# 01-Insence_Power.net
KiCad netlist of a schematic drawn in Altium Designer
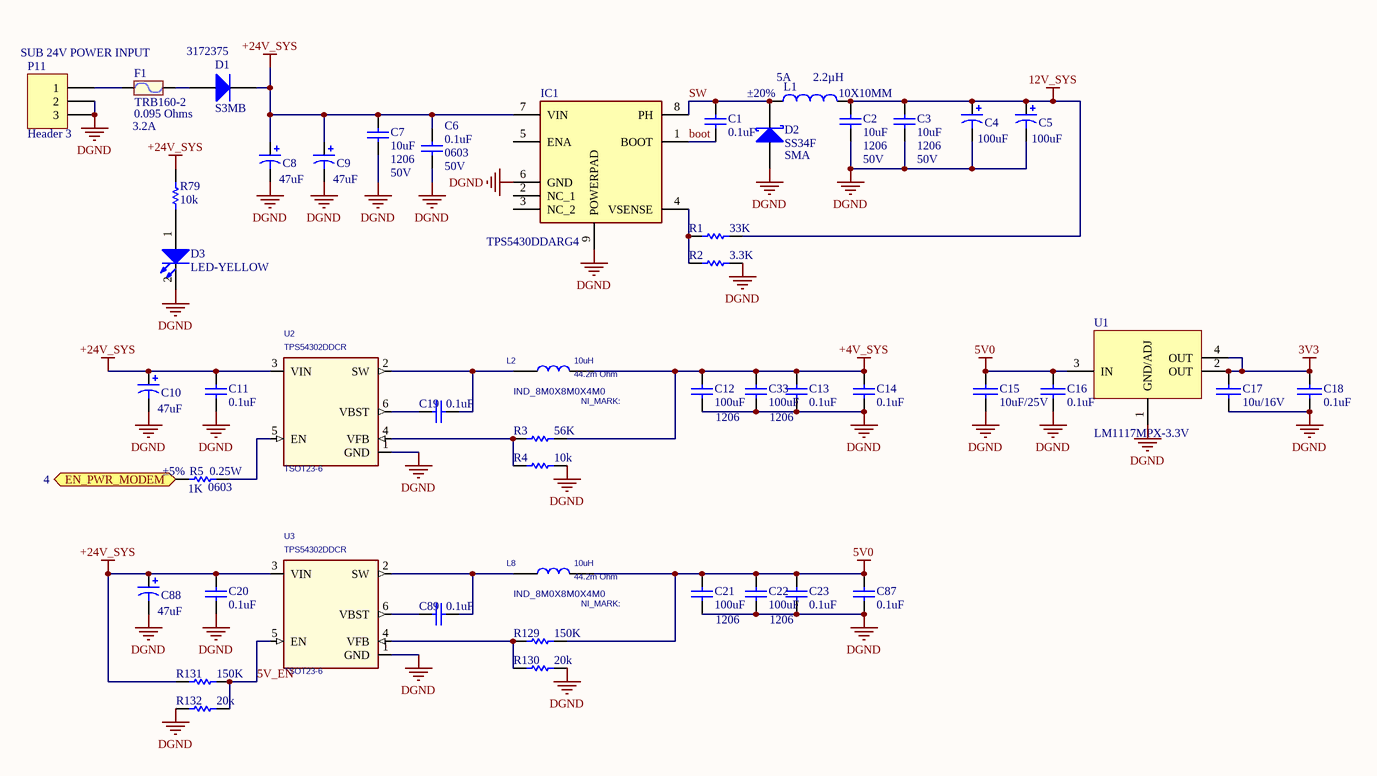
[diagram p0: 01-Insence_Power.SchDoc]

(export (version "E")
  (design (tool "Eeschema 10.0.6"))
  (components
    (comp (ref "C1")
      (value "Cap")
      (footprint "0805")
      (description "CAP CER 0.1UF 50V X7R 0805")
      (fields
        (field (name "=VALUE") "0.1uF")
        (field (name "MANUFACTURER1_PART#") "GMC21X7R104M50NT")
        (field (name "PUBLISHER") "Altium Limited")
      )
      (libsource (lib "Miscellaneous Devices") (part "Cap"))
    )
    (comp (ref "C2")
      (value "10uF")
      (footprint "1206")
      (description "CAP CER 10UF 50V X5R 1206")
      (fields
        (field (name "VOLTAGE") "50V")
        (field (name "TOLERANCE") "±10%")
        (field (name "MANUFACTURER1_PART#") "CL31A106MBHNNNE")
      )
      (libsource (lib "Slider") (part "Cap"))
    )
    (comp (ref "C3")
      (value "10uF")
      (footprint "1206")
      (description "CAP CER 10UF 50V X5R 1206")
      (fields
        (field (name "VOLTAGE") "50V")
        (field (name "TOLERANCE") "±10%")
        (field (name "MANUFACTURER1_PART#") "CL31A106MBHNNNE")
      )
      (libsource (lib "Slider") (part "Cap"))
    )
    (comp (ref "C4")
      (value "100uF")
      (footprint "CAP ALUM SMD-D Package 6.3x5.4mm")
      (description "CAP ALUM 100UF 20% 16V SMD")
      (fields
        (field (name "MANUFACTURER1_PART#") "UWX1C101MCL1GB")
        (field (name "MANUFACTURER2_PART#") "EDK107M016A9GAA")
      )
      (libsource (lib "My Library") (part "Cap TANTAN 100UF35V2917_1"))
    )
    (comp (ref "C5")
      (value "100uF")
      (footprint "CAP ALUM SMD-D Package 6.3x5.4mm")
      (description "CAP ALUM 100UF 20% 16V SMD")
      (fields
        (field (name "MANUFACTURER1_PART#") "UWX1C101MCL1GB")
        (field (name "MANUFACTURER2_PART#") "EDK107M016A9GAA")
      )
      (libsource (lib "My Library") (part "Cap TANTAN 100UF35V2917_1"))
    )
    (comp (ref "C6")
      (value "0.1uF")
      (footprint "0603")
      (description "CAP-CER,SMD;0.1UF,10%,50V,X7R,0603")
      (fields
        (field (name "VOLTAGE") "50V")
        (field (name "TOLERANCE") "±10%")
        (field (name "MANUFACTURER1_PART#") "CL10B104KB8NNNC")
      )
      (libsource (lib "Slider") (part "Cap"))
    )
    (comp (ref "C7")
      (value "10uF")
      (footprint "1206")
      (description "CAP CER 10UF 50V X5R 1206")
      (fields
        (field (name "VOLTAGE") "50V")
        (field (name "TOLERANCE") "±10%")
        (field (name "MANUFACTURER1_PART#") "CL31A106MBHNNNE")
      )
      (libsource (lib "Slider") (part "Cap"))
    )
    (comp (ref "C8")
      (value "47uF")
      (footprint "CAP ALUM SMD-D Package 6.3x5.4mm")
      (description "CAP ALUM 47UF 20% 35V SMD")
      (fields
        (field (name "MANUFACTURER1_PART#") "UUR1V470MCL6GS")
        (field (name "MANUFACTURER2_PART#") "EDK476M035A9GAA")
      )
      (libsource (lib "My Library") (part "Cap TANTAN 47UF35V2917"))
    )
    (comp (ref "C9")
      (value "47uF")
      (footprint "CAP ALUM SMD-D Package 6.3x5.4mm")
      (description "CAP ALUM 47UF 20% 35V SMD")
      (fields
        (field (name "MANUFACTURER1_PART#") "UUR1V470MCL6GS")
        (field (name "MANUFACTURER2_PART#") "EDK476M035A9GAA")
      )
      (libsource (lib "My Library") (part "Cap TANTAN 47UF35V2917"))
    )
    (comp (ref "C10")
      (value "47uF")
      (footprint "CAP ALUM SMD-D Package 6.3x5.4mm")
      (description "CAP ALUM 47UF 20% 35V SMD")
      (fields
        (field (name "MANUFACTURER1_PART#") "UUR1V470MCL6GS")
        (field (name "MANUFACTURER2_PART#") "EDK476M035A9GAA")
      )
      (libsource (lib "My Library") (part "Cap TANTAN 47UF35V2917"))
    )
    (comp (ref "C11")
      (value "Cap")
      (footprint "0805")
      (description "CAP CER 0.1UF 50V X7R 0805")
      (fields
        (field (name "=VALUE") "0.1uF")
        (field (name "MANUFACTURER1_PART#") "GMC21X7R104M50NT")
        (field (name "PUBLISHER") "Altium Limited")
      )
      (libsource (lib "Miscellaneous Devices") (part "Cap"))
    )
    (comp (ref "C12")
      (value "100uF")
      (footprint "CAP 1206")
      (description "CAP CER 100UF 6.3V X5R 1206")
      (fields
        (field (name "VOLTAGE") "6.3V")
        (field (name "PCB FOOTPRINT") "1206")
        (field (name "TOLERANCE") "±10%")
      )
      (libsource (lib "Slider") (part "Cap"))
    )
    (comp (ref "C13")
      (value "Cap")
      (footprint "0805")
      (description "CAP CER 0.1UF 50V X7R 0805")
      (fields
        (field (name "=VALUE") "0.1uF")
        (field (name "MANUFACTURER1_PART#") "GMC21X7R104M50NT")
        (field (name "PUBLISHER") "Altium Limited")
      )
      (libsource (lib "Miscellaneous Devices") (part "Cap"))
    )
    (comp (ref "C14")
      (value "Cap")
      (footprint "0805")
      (description "CAP CER 0.1UF 50V X7R 0805")
      (fields
        (field (name "=VALUE") "0.1uF")
        (field (name "MANUFACTURER1_PART#") "GMC21X7R104M50NT")
        (field (name "PUBLISHER") "Altium Limited")
      )
      (libsource (lib "Miscellaneous Devices") (part "Cap"))
    )
    (comp (ref "C15")
      (value "10uF/25V")
      (footprint "0805")
      (description "CAP CER 10UF 25V X5R 0805")
      (fields (field (name "MANUFACTURER1_PART#") "GMC21X5R106M25NT"))
      (libsource (lib "minhpv_sch") (part "CAP"))
    )
    (comp (ref "C16")
      (value "0.1uF")
      (footprint "0805")
      (description "CAP CER 0.1UF 50V X7R 0805")
      (fields (field (name "MANUFACTURER1_PART#") "GMC21X7R104M50NT"))
      (libsource (lib "minhpv_sch") (part "CAP"))
    )
    (comp (ref "C17")
      (value "10u/16V")
      (footprint "0805")
      (description "CAP CER 10UF 16V X5R 0805")
      (fields (field (name "MANUFACTURER1_PART#") "GMC21X5R106K16NT"))
      (libsource (lib "minhpv_sch") (part "CAP"))
    )
    (comp (ref "C18")
      (value "0.1uF")
      (footprint "0805")
      (description "CAP CER 0.1UF 50V X7R 0805")
      (fields (field (name "MANUFACTURER1_PART#") "GMC21X7R104M50NT"))
      (libsource (lib "minhpv_sch") (part "CAP"))
    )
    (comp (ref "C19")
      (value "Cap")
      (footprint "CAP 0603")
      (description "CAP CER 0.1UF 50V X5R 0603")
      (fields
        (field (name "=VALUE") "0.1uF")
        (field (name "MANUFACTURER1_PART#") "GMC10X5R104M50NT")
        (field (name "PUBLISHER") "Altium Limited")
      )
      (libsource (lib "Miscellaneous Devices") (part "Cap"))
    )
    (comp (ref "C20")
      (value "Cap")
      (footprint "0805")
      (description "CAP CER 0.1UF 50V X7R 0805")
      (fields
        (field (name "=VALUE") "0.1uF")
        (field (name "MANUFACTURER1_PART#") "GMC21X7R104M50NT")
        (field (name "PUBLISHER") "Altium Limited")
      )
      (libsource (lib "Miscellaneous Devices") (part "Cap"))
    )
    (comp (ref "C21")
      (value "100uF")
      (footprint "CAP 1206")
      (description "CAP CER 100UF 6.3V X5R 1206")
      (fields
        (field (name "VOLTAGE") "6.3V")
        (field (name "PCB FOOTPRINT") "1206")
        (field (name "TOLERANCE") "±10%")
      )
      (libsource (lib "Slider") (part "Cap"))
    )
    (comp (ref "C22")
      (value "100uF")
      (footprint "CAP 1206")
      (description "CAP CER 100UF 6.3V X5R 1206")
      (fields
        (field (name "VOLTAGE") "6.3V")
        (field (name "PCB FOOTPRINT") "1206")
        (field (name "TOLERANCE") "±10%")
      )
      (libsource (lib "Slider") (part "Cap"))
    )
    (comp (ref "C23")
      (value "Cap")
      (footprint "0805")
      (description "CAP CER 0.1UF 50V X7R 0805")
      (fields
        (field (name "=VALUE") "0.1uF")
        (field (name "MANUFACTURER1_PART#") "GMC21X7R104M50NT")
        (field (name "PUBLISHER") "Altium Limited")
      )
      (libsource (lib "Miscellaneous Devices") (part "Cap"))
    )
    (comp (ref "C33")
      (value "100uF")
      (footprint "CAP 1206")
      (description "CAP CER 100UF 6.3V X5R 1206")
      (fields
        (field (name "VOLTAGE") "6.3V")
        (field (name "PCB FOOTPRINT") "1206")
        (field (name "TOLERANCE") "±10%")
      )
      (libsource (lib "Slider") (part "Cap"))
    )
    (comp (ref "C87")
      (value "Cap")
      (footprint "0805")
      (description "CAP CER 0.1UF 50V X7R 0805")
      (fields
        (field (name "=VALUE") "0.1uF")
        (field (name "MANUFACTURER1_PART#") "GMC21X7R104M50NT")
        (field (name "PUBLISHER") "Altium Limited")
      )
      (libsource (lib "Miscellaneous Devices") (part "Cap"))
    )
    (comp (ref "C88")
      (value "47uF")
      (footprint "CAP ALUM SMD-D Package 6.3x5.4mm")
      (description "CAP ALUM 47UF 20% 35V SMD")
      (fields
        (field (name "MANUFACTURER1_PART#") "UUR1V470MCL6GS")
        (field (name "MANUFACTURER2_PART#") "EDK476M035A9GAA")
      )
      (libsource (lib "My Library") (part "Cap TANTAN 47UF35V2917"))
    )
    (comp (ref "C89")
      (value "Cap")
      (footprint "CAP 0603")
      (description "CAP CER 0.1UF 50V X5R 0603")
      (fields
        (field (name "=VALUE") "0.1uF")
        (field (name "MANUFACTURER1_PART#") "GMC10X5R104M50NT")
        (field (name "PUBLISHER") "Altium Limited")
      )
      (libsource (lib "Miscellaneous Devices") (part "Cap"))
    )
    (comp (ref "D1")
      (value "S3MB")
      (footprint "DO-214AB")
      (description "Default Diode")
      (fields
        (field (name "MANUFACTURER1_PART#") "S3MB-13-F")
        (field (name "SUPPLIER PART NUMBER 1") "3172375")
        (field (name "PUBLISHER") "Altium Limited")
      )
      (libsource (lib "Miscellaneous Devices") (part "Diode"))
    )
    (comp (ref "D2")
      (value "SS34F")
      (footprint "SMA")
      (description "Diode 40 V 3A Surface Mount SMAF")
      (fields (field (name "PACKAGEREFERENCE") "SMA") (field (name "PUBLISHER") "Altium Limited"))
      (libsource (lib "Miscellaneous Devices") (part "D Schottky"))
    )
    (comp (ref "D3")
      (value "LED-YELLOW")
      (footprint "led3mm_ra")
      (description "LED_3MM,2V,20mA,GREEN")
      (fields
        (field (name "MANUFACTURER1_PART#") "https://banlinhkien.com/led-3mm-xanh-la-duc-10c-p12117293.html")
      )
      (libsource (lib "VSM_SES-MAIN_REV04B") (part "LED-RED"))
    )
    (comp (ref "F1")
      (value "TRB160-2")
      (footprint "TRB160-2")
      (description "Polymeric 30V 3.2A 8s 95mO Through Hole,P=5.1mm,L=3.8mm PTC")
      (fields
        (field (name "MANUFACTURER2_PART#") "JK30-160")
        (field (name "DC COLD RESISTANCE") "0.095 Ohms")
        (field (name "CURRENT RATING (AMPS)") "3.2A")
      )
      (libsource (lib "K Shematic") (part "0875.800MXEP"))
    )
    (comp (ref "IC1")
      (value "TPS5430DDARG4")
      (footprint "Hiendv:SOIC127P600X170-9N")
      (description "Integrated Circuit")
      (fields (field (name "MOUSER PART NUMBER") "595-TPS5430DDARG4"))
      (libsource (lib "lib") (part "TPS5430DDARG4"))
    )
    (comp (ref "L1")
      (value "2.2µH")
      (footprint "IND 8x8MM")
      (description "FIXED IND 22UH 5A SMD 8x8mm")
      (fields
        (field (name "MANUFACTURER1_PART#") "SRP7050WA-220M")
        (field (name "PCB FOOTPRINT") "10X10MM")
        (field (name "RATE CURRENT") "5A")
        (field (name "TOLERANCE") "±20%")
      )
      (libsource (lib "Full") (part "inductor 2.2uF"))
    )
    (comp (ref "L2")
      (value "10uH")
      (footprint "IND 8x8MM")
      (description "IND-SMD;10uH,20%,8x8x4mm,3.1A,44.2mOHM")
      (fields
        (field (name "PACKAGE") "IND_8M0X8M0X4M0")
        (field (name "TOLERANCE") "20%")
        (field (name "MFG1_PART#") "NR8040T100M")
        (field (name "DCR") "44.2m Ohm")
        (field (name "BY") "VINFAST_RD")
      )
      (libsource (lib "*") (part "IND_10uH_3.1A_44.2mOhm_8MX8MX4M"))
    )
    (comp (ref "L8")
      (value "10uH")
      (footprint "IND 8x8MM")
      (description "IND-SMD;10uH,20%,8x8x4mm,3.1A,44.2mOHM")
      (fields
        (field (name "PACKAGE") "IND_8M0X8M0X4M0")
        (field (name "TOLERANCE") "20%")
        (field (name "MFG1_PART#") "NR8040T100M")
        (field (name "DCR") "44.2m Ohm")
        (field (name "BY") "VINFAST_RD")
      )
      (libsource (lib "*") (part "IND_10uH_3.1A_44.2mOhm_8MX8MX4M"))
    )
    (comp (ref "P11")
      (value "Header 3")
      (footprint "DC-in")
      (description "CONN PWR JACK 2X5.5MM SOLDER")
      (fields
        (field (name "MANUFACTURER1_PART#") "SCHURTER Inc.")
        (field (name "PUBLISHER") "Altium Limited")
      )
      (libsource (lib "Miscellaneous Connectors") (part "Header 3"))
    )
    (comp (ref "R1")
      (value "33K")
      (footprint "res 0603")
      (description "RES SMD 33K OHM 1% 1/10W 0603")
      (fields
        (field (name "MANUFACTURER1_PART#") "RM06F3302CT")
        (field (name "Comment") "Res1")
        (field (name "PUBLISHER") "Altium Limited")
      )
      (libsource (lib "Miscellaneous Devices") (part "Res1"))
    )
    (comp (ref "R2")
      (value "3.3K")
      (footprint "res 0603")
      (description "RES SMD 3.3K OHM 1% 1/10W 0603")
      (fields
        (field (name "MANUFACTURER1_PART#") "RM06F3301CT")
        (field (name "Comment") "Res1")
        (field (name "PUBLISHER") "Altium Limited")
      )
      (libsource (lib "Miscellaneous Devices") (part "Res1"))
    )
    (comp (ref "R3")
      (value "56K")
      (footprint "res 0603")
      (description "RES SMD 56K OHM 1% 1/10W 0603")
      (fields
        (field (name "MANUFACTURER1_PART#") "RM06F7322CT")
        (field (name "Comment") "Res1")
        (field (name "PUBLISHER") "Altium Limited")
      )
      (libsource (lib "Miscellaneous Devices") (part "Res1"))
    )
    (comp (ref "R4")
      (value "10k")
      (footprint "res 0603")
      (description "RES SMD 10K OHM 1% 1/10W 0603")
      (fields
        (field (name "MANUFACTURER1_PART#") "RM06F1302CT")
        (field (name "Comment") "Res1")
        (field (name "PUBLISHER") "Altium Limited")
      )
      (libsource (lib "Miscellaneous Devices") (part "Res1"))
    )
    (comp (ref "R5")
      (value "1K")
      (footprint "res 0603")
      (description "RES SMD,1K OHM,5%,1/10W,0603")
      (fields
        (field (name "MANUFACTURER1_PART#") "RMCF06031K00JNEAC")
        (field (name "MANUFACTURER2_PART#") "R0603J1KTG")
        (field (name "PCB FOOTPRINT") "0603")
        (field (name "POWER") "0.25W")
        (field (name "TOLERANCE") "±5%")
      )
      (libsource (lib "Full") (part "Res0.3"))
    )
    (comp (ref "R79")
      (value "10k")
      (footprint "res 0603")
      (description "RES SMD 10K OHM 1% 1/10W 0603")
      (fields
        (field (name "MANUFACTURER1_PART#") "RM06F1302CT")
        (field (name "Comment") "Res1")
        (field (name "PUBLISHER") "Altium Limited")
      )
      (libsource (lib "Miscellaneous Devices") (part "Res1"))
    )
    (comp (ref "R129")
      (value "150K")
      (footprint "res 0603")
      (description "RES SMD 56K OHM 1% 1/10W 0603")
      (fields
        (field (name "MANUFACTURER1_PART#") "RM06F7322CT")
        (field (name "Comment") "Res1")
        (field (name "PUBLISHER") "Altium Limited")
      )
      (libsource (lib "Miscellaneous Devices") (part "Res1"))
    )
    (comp (ref "R130")
      (value "20k")
      (footprint "res 0603")
      (description "RES SMD 10K OHM 1% 1/10W 0603")
      (fields
        (field (name "MANUFACTURER1_PART#") "RM06F1302CT")
        (field (name "Comment") "Res1")
        (field (name "PUBLISHER") "Altium Limited")
      )
      (libsource (lib "Miscellaneous Devices") (part "Res1"))
    )
    (comp (ref "R131")
      (value "150K")
      (footprint "res 0603")
      (description "RES SMD 56K OHM 1% 1/10W 0603")
      (fields
        (field (name "MANUFACTURER1_PART#") "RM06F7322CT")
        (field (name "Comment") "Res1")
        (field (name "PUBLISHER") "Altium Limited")
      )
      (libsource (lib "Miscellaneous Devices") (part "Res1"))
    )
    (comp (ref "R132")
      (value "20k")
      (footprint "res 0603")
      (description "RES SMD 10K OHM 1% 1/10W 0603")
      (fields
        (field (name "MANUFACTURER1_PART#") "RM06F1302CT")
        (field (name "Comment") "Res1")
        (field (name "PUBLISHER") "Altium Limited")
      )
      (libsource (lib "Miscellaneous Devices") (part "Res1"))
    )
    (comp (ref "U1")
      (value "LM1117MPX-3.3V")
      (footprint "SOT223")
      (description "LDO, LM1117MPX-3.3V")
      (libsource (lib "lib") (part "LM1117"))
    )
    (comp (ref "U2")
      (value "TPS54302DDCR")
      (footprint "SOT23-6")
      (description "IC REG BUCK ADJ 3A TSOT23-6,TPS54302DDCR")
      (fields
        (field (name "DISTR1_PART#") "296-46237-1-ND")
        (field (name "PACKAGE") "TSOT23-6")
        (field (name "BY") "VINFAST_RD")
      )
      (libsource (lib "*") (part "IC_TPS54302DDCR"))
    )
    (comp (ref "U3")
      (value "TPS54302DDCR")
      (footprint "SOT23-6")
      (description "IC REG BUCK ADJ 3A TSOT23-6,TPS54302DDCR")
      (fields
        (field (name "DISTR1_PART#") "296-46237-1-ND")
        (field (name "PACKAGE") "TSOT23-6")
        (field (name "BY") "VINFAST_RD")
      )
      (libsource (lib "*") (part "IC_TPS54302DDCR"))
    )
  )
  (nets
    (net (code "1") (name "+4V_SYS") (class "Default")
      (node (ref "C12") (pin "1") (pinfunction "1_1") (pintype "passive"))
      (node (ref "C13") (pin "2") (pinfunction "2_2") (pintype "passive"))
      (node (ref "C14") (pin "2") (pinfunction "2_2") (pintype "passive"))
      (node (ref "C33") (pin "1") (pinfunction "1_1") (pintype "passive"))
      (node (ref "L2") (pin "2") (pinfunction "B_2") (pintype "passive"))
      (node (ref "R3") (pin "2") (pinfunction "2_2") (pintype "passive"))
    )
    (net (code "2") (name "+24V_SYS") (class "Default")
      (node (ref "C10") (pin "1") (pinfunction "1_1") (pintype "passive"))
      (node (ref "C11") (pin "2") (pinfunction "2_2") (pintype "passive"))
      (node (ref "C20") (pin "2") (pinfunction "2_2") (pintype "passive"))
      (node (ref "C6") (pin "2") (pinfunction "2_2") (pintype "passive"))
      (node (ref "C7") (pin "2") (pinfunction "2_2") (pintype "passive"))
      (node (ref "C8") (pin "1") (pinfunction "1_1") (pintype "passive"))
      (node (ref "C88") (pin "1") (pinfunction "1_1") (pintype "passive"))
      (node (ref "C9") (pin "1") (pinfunction "1_1") (pintype "passive"))
      (node (ref "D1") (pin "2") (pinfunction "K_2") (pintype "passive"))
      (node (ref "IC1") (pin "7") (pinfunction "VIN_7") (pintype "passive"))
      (node (ref "R131") (pin "1") (pinfunction "1_1") (pintype "passive"))
      (node (ref "R79") (pin "2") (pinfunction "2_2") (pintype "passive"))
      (node (ref "U2") (pin "3") (pinfunction "VIN_3") (pintype "power_in"))
      (node (ref "U3") (pin "3") (pinfunction "VIN_3") (pintype "power_in"))
    )
    (net (code "3") (name "/5V_EN") (class "Default")
      (node (ref "R131") (pin "2") (pinfunction "2_2") (pintype "passive"))
      (node (ref "R132") (pin "2") (pinfunction "2_2") (pintype "passive"))
      (node (ref "U3") (pin "5") (pinfunction "EN_5") (pintype "input"))
    )
    (net (code "4") (name "/EN_PWR_MODEM") (class "Default")
      (node (ref "R5") (pin "2") (pinfunction "2_2") (pintype "passive"))
    )
    (net (code "5") (name "/SW") (class "Default")
      (node (ref "C1") (pin "2") (pinfunction "2_2") (pintype "passive"))
      (node (ref "D2") (pin "2") (pinfunction "K_2") (pintype "passive"))
      (node (ref "IC1") (pin "8") (pinfunction "PH_8") (pintype "passive"))
      (node (ref "L1") (pin "1") (pinfunction "1_1") (pintype "passive"))
    )
    (net (code "6") (name "/boot") (class "Default")
      (node (ref "C1") (pin "1") (pinfunction "1_1") (pintype "passive"))
      (node (ref "IC1") (pin "1") (pinfunction "BOOT_1") (pintype "passive"))
    )
    (net (code "7") (name "3V3") (class "Default")
      (node (ref "C17") (pin "1") (pinfunction "1_1") (pintype "passive"))
      (node (ref "C18") (pin "1") (pinfunction "1_1") (pintype "passive"))
      (node (ref "U1") (pin "2") (pinfunction "OUT_2") (pintype "passive"))
      (node (ref "U1") (pin "4") (pinfunction "OUT_4") (pintype "passive"))
    )
    (net (code "8") (name "5V0") (class "Default")
      (node (ref "C15") (pin "1") (pinfunction "1_1") (pintype "passive"))
      (node (ref "C16") (pin "1") (pinfunction "1_1") (pintype "passive"))
      (node (ref "C21") (pin "1") (pinfunction "1_1") (pintype "passive"))
      (node (ref "C22") (pin "1") (pinfunction "1_1") (pintype "passive"))
      (node (ref "C23") (pin "2") (pinfunction "2_2") (pintype "passive"))
      (node (ref "C87") (pin "2") (pinfunction "2_2") (pintype "passive"))
      (node (ref "L8") (pin "2") (pinfunction "B_2") (pintype "passive"))
      (node (ref "R129") (pin "2") (pinfunction "2_2") (pintype "passive"))
      (node (ref "U1") (pin "3") (pinfunction "IN_3") (pintype "passive"))
    )
    (net (code "9") (name "12V_SYS") (class "Default")
      (node (ref "C2") (pin "2") (pinfunction "2_2") (pintype "passive"))
      (node (ref "C3") (pin "2") (pinfunction "2_2") (pintype "passive"))
      (node (ref "C4") (pin "1") (pinfunction "1_1") (pintype "passive"))
      (node (ref "C5") (pin "1") (pinfunction "1_1") (pintype "passive"))
      (node (ref "L1") (pin "2") (pinfunction "2_2") (pintype "passive"))
      (node (ref "R1") (pin "2") (pinfunction "2_2") (pintype "passive"))
    )
    (net (code "10") (name "DGND") (class "Default")
      (node (ref "C10") (pin "2") (pinfunction "2_2") (pintype "passive"))
      (node (ref "C11") (pin "1") (pinfunction "1_1") (pintype "passive"))
      (node (ref "C12") (pin "2") (pinfunction "2_2") (pintype "passive"))
      (node (ref "C13") (pin "1") (pinfunction "1_1") (pintype "passive"))
      (node (ref "C14") (pin "1") (pinfunction "1_1") (pintype "passive"))
      (node (ref "C15") (pin "2") (pinfunction "2_2") (pintype "passive"))
      (node (ref "C16") (pin "2") (pinfunction "2_2") (pintype "passive"))
      (node (ref "C17") (pin "2") (pinfunction "2_2") (pintype "passive"))
      (node (ref "C18") (pin "2") (pinfunction "2_2") (pintype "passive"))
      (node (ref "C2") (pin "1") (pinfunction "1_1") (pintype "passive"))
      (node (ref "C20") (pin "1") (pinfunction "1_1") (pintype "passive"))
      (node (ref "C21") (pin "2") (pinfunction "2_2") (pintype "passive"))
      (node (ref "C22") (pin "2") (pinfunction "2_2") (pintype "passive"))
      (node (ref "C23") (pin "1") (pinfunction "1_1") (pintype "passive"))
      (node (ref "C3") (pin "1") (pinfunction "1_1") (pintype "passive"))
      (node (ref "C33") (pin "2") (pinfunction "2_2") (pintype "passive"))
      (node (ref "C4") (pin "2") (pinfunction "2_2") (pintype "passive"))
      (node (ref "C5") (pin "2") (pinfunction "2_2") (pintype "passive"))
      (node (ref "C6") (pin "1") (pinfunction "1_1") (pintype "passive"))
      (node (ref "C7") (pin "1") (pinfunction "1_1") (pintype "passive"))
      (node (ref "C8") (pin "2") (pinfunction "2_2") (pintype "passive"))
      (node (ref "C87") (pin "1") (pinfunction "1_1") (pintype "passive"))
      (node (ref "C88") (pin "2") (pinfunction "2_2") (pintype "passive"))
      (node (ref "C9") (pin "2") (pinfunction "2_2") (pintype "passive"))
      (node (ref "D2") (pin "1") (pinfunction "A_1") (pintype "passive"))
      (node (ref "D3") (pin "2") (pinfunction "K_2") (pintype "passive"))
      (node (ref "IC1") (pin "6") (pinfunction "GND_6") (pintype "passive"))
      (node (ref "IC1") (pin "9") (pinfunction "POWERPAD_9") (pintype "passive"))
      (node (ref "P11") (pin "2") (pinfunction "2_2") (pintype "passive"))
      (node (ref "P11") (pin "3") (pinfunction "3_3") (pintype "passive"))
      (node (ref "R130") (pin "2") (pinfunction "2_2") (pintype "passive"))
      (node (ref "R132") (pin "1") (pinfunction "1_1") (pintype "passive"))
      (node (ref "R2") (pin "2") (pinfunction "2_2") (pintype "passive"))
      (node (ref "R4") (pin "2") (pinfunction "2_2") (pintype "passive"))
      (node (ref "U1") (pin "1") (pinfunction "GND/ADJ_1") (pintype "passive"))
      (node (ref "U2") (pin "1") (pinfunction "GND_1") (pintype "power_in"))
      (node (ref "U3") (pin "1") (pinfunction "GND_1") (pintype "power_in"))
    )
    (net (code "11") (name "Net-(D1-A)") (class "Default")
      (node (ref "D1") (pin "1") (pinfunction "A_1") (pintype "passive"))
      (node (ref "F1") (pin "2") (pinfunction "2_2") (pintype "passive"))
    )
    (net (code "12") (name "Net-(D3-A)") (class "Default")
      (node (ref "D3") (pin "1") (pinfunction "A_1") (pintype "passive"))
      (node (ref "R79") (pin "1") (pinfunction "1_1") (pintype "passive"))
    )
    (net (code "13") (name "Net-(F1-Pad1)") (class "Default")
      (node (ref "F1") (pin "1") (pinfunction "1_1") (pintype "passive"))
      (node (ref "P11") (pin "1") (pinfunction "1_1") (pintype "passive"))
    )
    (net (code "14") (name "Net-(IC1-VSENSE)") (class "Default")
      (node (ref "IC1") (pin "4") (pinfunction "VSENSE_4") (pintype "passive"))
      (node (ref "R1") (pin "1") (pinfunction "1_1") (pintype "passive"))
      (node (ref "R2") (pin "1") (pinfunction "1_1") (pintype "passive"))
    )
    (net (code "15") (name "Net-(L2-A)") (class "Default")
      (node (ref "C19") (pin "2") (pinfunction "2_2") (pintype "passive"))
      (node (ref "L2") (pin "1") (pinfunction "A_1") (pintype "passive"))
      (node (ref "U2") (pin "2") (pinfunction "SW_2") (pintype "output"))
    )
    (net (code "16") (name "Net-(L8-A)") (class "Default")
      (node (ref "C89") (pin "2") (pinfunction "2_2") (pintype "passive"))
      (node (ref "L8") (pin "1") (pinfunction "A_1") (pintype "passive"))
      (node (ref "U3") (pin "2") (pinfunction "SW_2") (pintype "output"))
    )
    (net (code "17") (name "Net-(U2-EN)") (class "Default")
      (node (ref "R5") (pin "1") (pinfunction "1_1") (pintype "passive"))
      (node (ref "U2") (pin "5") (pinfunction "EN_5") (pintype "input"))
    )
    (net (code "18") (name "Net-(U2-VBST)") (class "Default")
      (node (ref "C19") (pin "1") (pinfunction "1_1") (pintype "passive"))
      (node (ref "U2") (pin "6") (pinfunction "VBST_6") (pintype "output"))
    )
    (net (code "19") (name "Net-(U2-VFB)") (class "Default")
      (node (ref "R3") (pin "1") (pinfunction "1_1") (pintype "passive"))
      (node (ref "R4") (pin "1") (pinfunction "1_1") (pintype "passive"))
      (node (ref "U2") (pin "4") (pinfunction "VFB_4") (pintype "input"))
    )
    (net (code "20") (name "Net-(U3-VBST)") (class "Default")
      (node (ref "C89") (pin "1") (pinfunction "1_1") (pintype "passive"))
      (node (ref "U3") (pin "6") (pinfunction "VBST_6") (pintype "output"))
    )
    (net (code "21") (name "Net-(U3-VFB)") (class "Default")
      (node (ref "R129") (pin "1") (pinfunction "1_1") (pintype "passive"))
      (node (ref "R130") (pin "1") (pinfunction "1_1") (pintype "passive"))
      (node (ref "U3") (pin "4") (pinfunction "VFB_4") (pintype "input"))
    )
    (net (code "22") (name "unconnected-(IC1-ENA-Pad5)") (class "Default")
      (node (ref "IC1") (pin "5") (pinfunction "ENA_5") (pintype "passive"))
    )
    (net (code "23") (name "unconnected-(IC1-NC_1-Pad2)") (class "Default")
      (node (ref "IC1") (pin "2") (pinfunction "NC_1_2") (pintype "passive"))
    )
    (net (code "24") (name "unconnected-(IC1-NC_2-Pad3)") (class "Default")
      (node (ref "IC1") (pin "3") (pinfunction "NC_2_3") (pintype "passive"))
    )
  )
)
